# ServoShield_Protorype.net
KiCad netlist of a schematic drawn in EAGLE
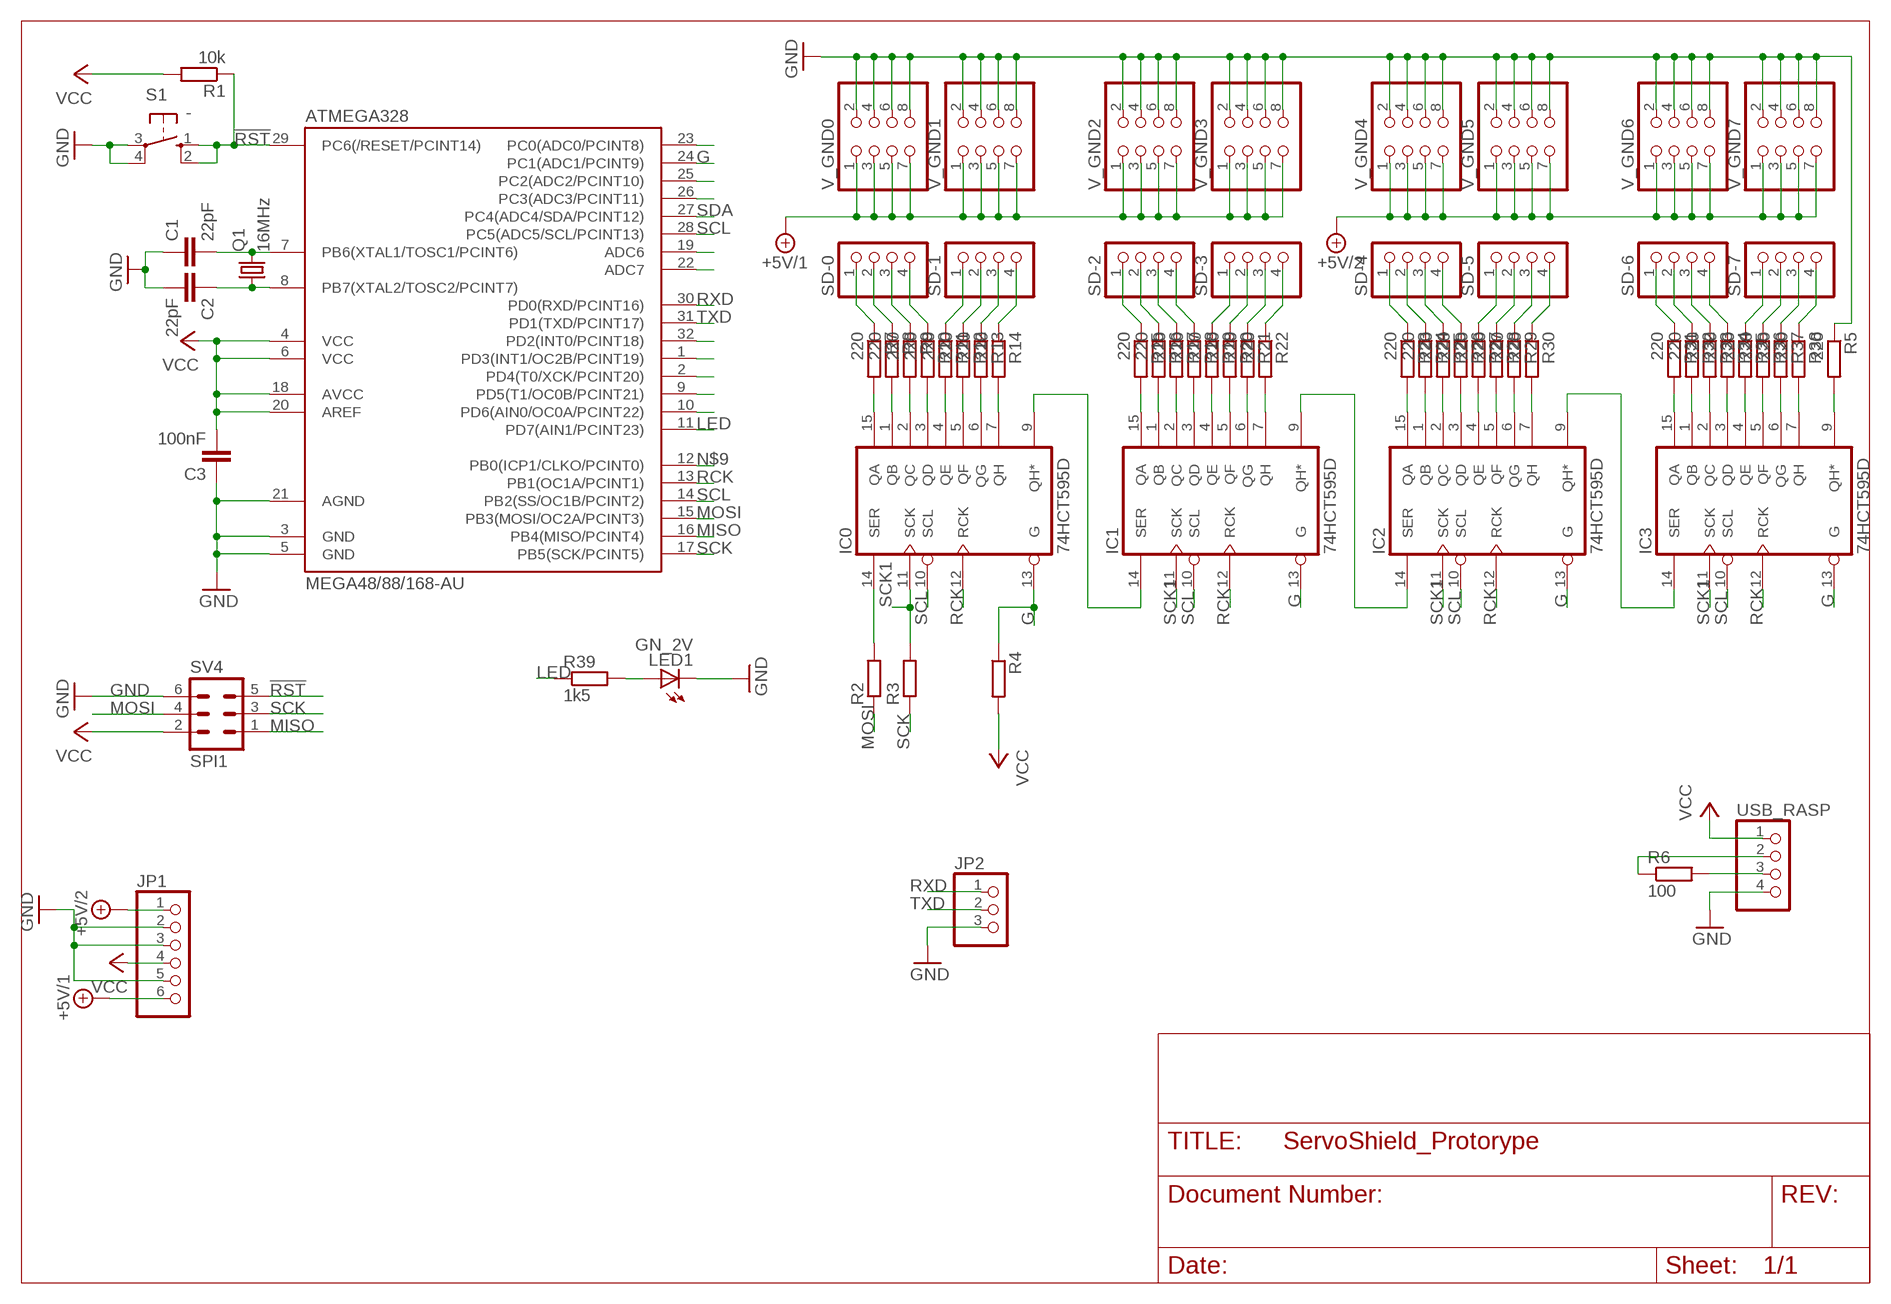
[diagram p0: schematic, sheet 1]

(export (version "E")
  (design (tool "Eeschema 10.0.6"))
  (components
    (comp (ref "ATMEGA328")
      (value "MEGA48/88/168-AU")
      (footprint "eagle-import:TQFP32-08")
      (libsource (lib "eagle-import") (part "MEGA48/88/168-AU"))
    )
    (comp (ref "C1")
      (value "22pF")
      (footprint "eagle-import:C0805")
      (libsource (lib "eagle-import") (part "C-EUC0805"))
    )
    (comp (ref "C2")
      (value "22pF")
      (footprint "eagle-import:C0805")
      (libsource (lib "eagle-import") (part "C-EUC0805"))
    )
    (comp (ref "C3")
      (value "100nF")
      (footprint "eagle-import:C0805")
      (libsource (lib "eagle-import") (part "resistor_C-EUC0805"))
    )
    (comp (ref "IC0")
      (value "74HCT595D")
      (footprint "eagle-import:SO16")
      (libsource (lib "eagle-import") (part "74595DHCT"))
    )
    (comp (ref "IC1")
      (value "74HCT595D")
      (footprint "eagle-import:SO16")
      (libsource (lib "eagle-import") (part "74595DHCT"))
    )
    (comp (ref "IC2")
      (value "74HCT595D")
      (footprint "eagle-import:SO16")
      (libsource (lib "eagle-import") (part "74595DHCT"))
    )
    (comp (ref "IC3")
      (value "74HCT595D")
      (footprint "eagle-import:SO16")
      (libsource (lib "eagle-import") (part "74595DHCT"))
    )
    (comp (ref "JP1")
      (value "PINHD-1X6")
      (footprint "eagle-import:1X06")
      (libsource (lib "eagle-import") (part "PINHD-1X6"))
    )
    (comp (ref "JP2")
      (value "PINHD-1X3")
      (footprint "eagle-import:1X03")
      (libsource (lib "eagle-import") (part "PINHD-1X3"))
    )
    (comp (ref "LED1")
      (value "GN_2V")
      (footprint "eagle-import:LED3MM")
      (libsource (lib "eagle-import") (part "LED3MM"))
    )
    (comp (ref "Q1")
      (value "16MHz")
      (footprint "eagle-import:HC49UP")
      (libsource (lib "eagle-import") (part "CRYSTALHC49UP"))
    )
    (comp (ref "R1")
      (value "10k")
      (footprint "eagle-import:R0805")
      (libsource (lib "eagle-import") (part "resistor_R-EU_R0805"))
    )
    (comp (ref "R2")
      (value "R-EU_R0805")
      (footprint "eagle-import:R0805")
      (libsource (lib "eagle-import") (part "R-EU_R0805"))
    )
    (comp (ref "R3")
      (value "R-EU_R0805")
      (footprint "eagle-import:R0805")
      (libsource (lib "eagle-import") (part "R-EU_R0805"))
    )
    (comp (ref "R4")
      (value "R-EU_R0805")
      (footprint "eagle-import:R0805")
      (libsource (lib "eagle-import") (part "R-EU_R0805"))
    )
    (comp (ref "R5")
      (value "220")
      (footprint "eagle-import:R0805")
      (libsource (lib "eagle-import") (part "R-EU_R0805"))
    )
    (comp (ref "R6")
      (value "100")
      (footprint "eagle-import:R0805")
      (libsource (lib "eagle-import") (part "R-EU_R0805"))
    )
    (comp (ref "R7")
      (value "220")
      (footprint "eagle-import:R0805")
      (libsource (lib "eagle-import") (part "R-EU_R0805"))
    )
    (comp (ref "R8")
      (value "220")
      (footprint "eagle-import:R0805")
      (libsource (lib "eagle-import") (part "R-EU_R0805"))
    )
    (comp (ref "R9")
      (value "220")
      (footprint "eagle-import:R0805")
      (libsource (lib "eagle-import") (part "R-EU_R0805"))
    )
    (comp (ref "R10")
      (value "220")
      (footprint "eagle-import:R0805")
      (libsource (lib "eagle-import") (part "R-EU_R0805"))
    )
    (comp (ref "R11")
      (value "220")
      (footprint "eagle-import:R0805")
      (libsource (lib "eagle-import") (part "R-EU_R0805"))
    )
    (comp (ref "R12")
      (value "220")
      (footprint "eagle-import:R0805")
      (libsource (lib "eagle-import") (part "R-EU_R0805"))
    )
    (comp (ref "R13")
      (value "220")
      (footprint "eagle-import:R0805")
      (libsource (lib "eagle-import") (part "R-EU_R0805"))
    )
    (comp (ref "R14")
      (value "220")
      (footprint "eagle-import:R0805")
      (libsource (lib "eagle-import") (part "R-EU_R0805"))
    )
    (comp (ref "R15")
      (value "220")
      (footprint "eagle-import:R0805")
      (libsource (lib "eagle-import") (part "R-EU_R0805"))
    )
    (comp (ref "R16")
      (value "220")
      (footprint "eagle-import:R0805")
      (libsource (lib "eagle-import") (part "R-EU_R0805"))
    )
    (comp (ref "R17")
      (value "220")
      (footprint "eagle-import:R0805")
      (libsource (lib "eagle-import") (part "R-EU_R0805"))
    )
    (comp (ref "R18")
      (value "220")
      (footprint "eagle-import:R0805")
      (libsource (lib "eagle-import") (part "R-EU_R0805"))
    )
    (comp (ref "R19")
      (value "220")
      (footprint "eagle-import:R0805")
      (libsource (lib "eagle-import") (part "R-EU_R0805"))
    )
    (comp (ref "R20")
      (value "220")
      (footprint "eagle-import:R0805")
      (libsource (lib "eagle-import") (part "R-EU_R0805"))
    )
    (comp (ref "R21")
      (value "220")
      (footprint "eagle-import:R0805")
      (libsource (lib "eagle-import") (part "R-EU_R0805"))
    )
    (comp (ref "R22")
      (value "220")
      (footprint "eagle-import:R0805")
      (libsource (lib "eagle-import") (part "R-EU_R0805"))
    )
    (comp (ref "R23")
      (value "220")
      (footprint "eagle-import:R0805")
      (libsource (lib "eagle-import") (part "R-EU_R0805"))
    )
    (comp (ref "R24")
      (value "220")
      (footprint "eagle-import:R0805")
      (libsource (lib "eagle-import") (part "R-EU_R0805"))
    )
    (comp (ref "R25")
      (value "220")
      (footprint "eagle-import:R0805")
      (libsource (lib "eagle-import") (part "R-EU_R0805"))
    )
    (comp (ref "R26")
      (value "220")
      (footprint "eagle-import:R0805")
      (libsource (lib "eagle-import") (part "R-EU_R0805"))
    )
    (comp (ref "R27")
      (value "220")
      (footprint "eagle-import:R0805")
      (libsource (lib "eagle-import") (part "R-EU_R0805"))
    )
    (comp (ref "R28")
      (value "220")
      (footprint "eagle-import:R0805")
      (libsource (lib "eagle-import") (part "R-EU_R0805"))
    )
    (comp (ref "R29")
      (value "220")
      (footprint "eagle-import:R0805")
      (libsource (lib "eagle-import") (part "R-EU_R0805"))
    )
    (comp (ref "R30")
      (value "220")
      (footprint "eagle-import:R0805")
      (libsource (lib "eagle-import") (part "R-EU_R0805"))
    )
    (comp (ref "R31")
      (value "220")
      (footprint "eagle-import:R0805")
      (libsource (lib "eagle-import") (part "R-EU_R0805"))
    )
    (comp (ref "R32")
      (value "220")
      (footprint "eagle-import:R0805")
      (libsource (lib "eagle-import") (part "R-EU_R0805"))
    )
    (comp (ref "R33")
      (value "220")
      (footprint "eagle-import:R0805")
      (libsource (lib "eagle-import") (part "R-EU_R0805"))
    )
    (comp (ref "R34")
      (value "220")
      (footprint "eagle-import:R0805")
      (libsource (lib "eagle-import") (part "R-EU_R0805"))
    )
    (comp (ref "R35")
      (value "220")
      (footprint "eagle-import:R0805")
      (libsource (lib "eagle-import") (part "R-EU_R0805"))
    )
    (comp (ref "R36")
      (value "220")
      (footprint "eagle-import:R0805")
      (libsource (lib "eagle-import") (part "R-EU_R0805"))
    )
    (comp (ref "R37")
      (value "220")
      (footprint "eagle-import:R0805")
      (libsource (lib "eagle-import") (part "R-EU_R0805"))
    )
    (comp (ref "R38")
      (value "220")
      (footprint "eagle-import:R0805")
      (libsource (lib "eagle-import") (part "R-EU_R0805"))
    )
    (comp (ref "R39")
      (value "1k5")
      (footprint "eagle-import:R0805")
      (libsource (lib "eagle-import") (part "R-EU_R0805"))
    )
    (comp (ref "S1")
      (value "-")
      (footprint "eagle-import:B3F-10XX")
      (fields (field (name "MPN") "B3F-1000"))
      (libsource (lib "eagle-import") (part "10-XX"))
    )
    (comp (ref "SD-0")
      (value "PINHD-1X4")
      (footprint "eagle-import:1X04")
      (libsource (lib "eagle-import") (part "PINHD-1X4"))
    )
    (comp (ref "SD-1")
      (value "PINHD-1X4")
      (footprint "eagle-import:1X04")
      (libsource (lib "eagle-import") (part "PINHD-1X4"))
    )
    (comp (ref "SD-2")
      (value "PINHD-1X4")
      (footprint "eagle-import:1X04")
      (libsource (lib "eagle-import") (part "PINHD-1X4"))
    )
    (comp (ref "SD-3")
      (value "PINHD-1X4")
      (footprint "eagle-import:1X04")
      (libsource (lib "eagle-import") (part "PINHD-1X4"))
    )
    (comp (ref "SD-4")
      (value "PINHD-1X4")
      (footprint "eagle-import:1X04")
      (libsource (lib "eagle-import") (part "PINHD-1X4"))
    )
    (comp (ref "SD-5")
      (value "PINHD-1X4")
      (footprint "eagle-import:1X04")
      (libsource (lib "eagle-import") (part "PINHD-1X4"))
    )
    (comp (ref "SD-6")
      (value "PINHD-1X4")
      (footprint "eagle-import:1X04")
      (libsource (lib "eagle-import") (part "PINHD-1X4"))
    )
    (comp (ref "SD-7")
      (value "PINHD-1X4")
      (footprint "eagle-import:1X04")
      (libsource (lib "eagle-import") (part "PINHD-1X4"))
    )
    (comp (ref "SV4")
      (value "SPI1")
      (footprint "eagle-import:ML6")
      (libsource (lib "eagle-import") (part "ML6"))
    )
    (comp (ref "USB_RASP")
      (value "PINHD-1X4")
      (footprint "eagle-import:1X04")
      (libsource (lib "eagle-import") (part "PINHD-1X4"))
    )
    (comp (ref "V_GND0")
      (value "PINHD-2X4")
      (footprint "eagle-import:2X04")
      (libsource (lib "eagle-import") (part "PINHD-2X4"))
    )
    (comp (ref "V_GND1")
      (value "PINHD-2X4")
      (footprint "eagle-import:2X04")
      (libsource (lib "eagle-import") (part "PINHD-2X4"))
    )
    (comp (ref "V_GND2")
      (value "PINHD-2X4")
      (footprint "eagle-import:2X04")
      (libsource (lib "eagle-import") (part "PINHD-2X4"))
    )
    (comp (ref "V_GND3")
      (value "PINHD-2X4")
      (footprint "eagle-import:2X04")
      (libsource (lib "eagle-import") (part "PINHD-2X4"))
    )
    (comp (ref "V_GND4")
      (value "PINHD-2X4")
      (footprint "eagle-import:2X04")
      (libsource (lib "eagle-import") (part "PINHD-2X4"))
    )
    (comp (ref "V_GND5")
      (value "PINHD-2X4")
      (footprint "eagle-import:2X04")
      (libsource (lib "eagle-import") (part "PINHD-2X4"))
    )
    (comp (ref "V_GND6")
      (value "PINHD-2X4")
      (footprint "eagle-import:2X04")
      (libsource (lib "eagle-import") (part "PINHD-2X4"))
    )
    (comp (ref "V_GND7")
      (value "PINHD-2X4")
      (footprint "eagle-import:2X04")
      (libsource (lib "eagle-import") (part "PINHD-2X4"))
    )
  )
  (nets
    (net (code "1") (name "+5V{slash}1") (class "Default")
      (node (ref "JP1") (pin "6") (pinfunction "6_6") (pintype "passive"))
      (node (ref "V_GND0") (pin "1") (pinfunction "1_1") (pintype "passive"))
      (node (ref "V_GND0") (pin "3") (pinfunction "3_3") (pintype "passive"))
      (node (ref "V_GND0") (pin "5") (pinfunction "5_5") (pintype "passive"))
      (node (ref "V_GND0") (pin "7") (pinfunction "7_7") (pintype "passive"))
      (node (ref "V_GND1") (pin "1") (pinfunction "1_1") (pintype "passive"))
      (node (ref "V_GND1") (pin "3") (pinfunction "3_3") (pintype "passive"))
      (node (ref "V_GND1") (pin "5") (pinfunction "5_5") (pintype "passive"))
      (node (ref "V_GND1") (pin "7") (pinfunction "7_7") (pintype "passive"))
      (node (ref "V_GND2") (pin "1") (pinfunction "1_1") (pintype "passive"))
      (node (ref "V_GND2") (pin "3") (pinfunction "3_3") (pintype "passive"))
      (node (ref "V_GND2") (pin "5") (pinfunction "5_5") (pintype "passive"))
      (node (ref "V_GND2") (pin "7") (pinfunction "7_7") (pintype "passive"))
      (node (ref "V_GND3") (pin "1") (pinfunction "1_1") (pintype "passive"))
      (node (ref "V_GND3") (pin "3") (pinfunction "3_3") (pintype "passive"))
      (node (ref "V_GND3") (pin "5") (pinfunction "5_5") (pintype "passive"))
      (node (ref "V_GND3") (pin "7") (pinfunction "7_7") (pintype "passive"))
    )
    (net (code "2") (name "+5V{slash}2") (class "Default")
      (node (ref "JP1") (pin "1") (pinfunction "1_1") (pintype "passive"))
      (node (ref "V_GND4") (pin "1") (pinfunction "1_1") (pintype "passive"))
      (node (ref "V_GND4") (pin "3") (pinfunction "3_3") (pintype "passive"))
      (node (ref "V_GND4") (pin "5") (pinfunction "5_5") (pintype "passive"))
      (node (ref "V_GND4") (pin "7") (pinfunction "7_7") (pintype "passive"))
      (node (ref "V_GND5") (pin "1") (pinfunction "1_1") (pintype "passive"))
      (node (ref "V_GND5") (pin "3") (pinfunction "3_3") (pintype "passive"))
      (node (ref "V_GND5") (pin "5") (pinfunction "5_5") (pintype "passive"))
      (node (ref "V_GND5") (pin "7") (pinfunction "7_7") (pintype "passive"))
      (node (ref "V_GND6") (pin "1") (pinfunction "1_1") (pintype "passive"))
      (node (ref "V_GND6") (pin "3") (pinfunction "3_3") (pintype "passive"))
      (node (ref "V_GND6") (pin "5") (pinfunction "5_5") (pintype "passive"))
      (node (ref "V_GND6") (pin "7") (pinfunction "7_7") (pintype "passive"))
      (node (ref "V_GND7") (pin "1") (pinfunction "1_1") (pintype "passive"))
      (node (ref "V_GND7") (pin "3") (pinfunction "3_3") (pintype "passive"))
      (node (ref "V_GND7") (pin "5") (pinfunction "5_5") (pintype "passive"))
      (node (ref "V_GND7") (pin "7") (pinfunction "7_7") (pintype "passive"))
    )
    (net (code "3") (name "/G") (class "Default")
      (node (ref "ATMEGA328") (pin "24") (pinfunction "PC1(ADC1/PCINT9)_24") (pintype "bidirectional"))
      (node (ref "IC0") (pin "13") (pinfunction "G_13") (pintype "input"))
      (node (ref "IC1") (pin "13") (pinfunction "G_13") (pintype "input"))
      (node (ref "IC2") (pin "13") (pinfunction "G_13") (pintype "input"))
      (node (ref "IC3") (pin "13") (pinfunction "G_13") (pintype "input"))
      (node (ref "R4") (pin "1") (pinfunction "1_1") (pintype "passive"))
    )
    (net (code "4") (name "/LED") (class "Default")
      (node (ref "ATMEGA328") (pin "11") (pinfunction "PD7(AIN1/PCINT23)_11") (pintype "bidirectional"))
      (node (ref "R39") (pin "1") (pinfunction "1_1") (pintype "passive"))
    )
    (net (code "5") (name "/MISO") (class "Default")
      (node (ref "ATMEGA328") (pin "16") (pinfunction "PB4(MISO/PCINT4)_16") (pintype "bidirectional"))
      (node (ref "SV4") (pin "1") (pinfunction "1_1") (pintype "passive"))
    )
    (net (code "6") (name "/MOSI") (class "Default")
      (node (ref "ATMEGA328") (pin "15") (pinfunction "PB3(MOSI/OC2A/PCINT3)_15") (pintype "bidirectional"))
      (node (ref "R2") (pin "1") (pinfunction "1_1") (pintype "passive"))
      (node (ref "SV4") (pin "4") (pinfunction "4_4") (pintype "passive"))
    )
    (net (code "7") (name "/N$9") (class "Default")
      (node (ref "ATMEGA328") (pin "12") (pinfunction "PB0(ICP1/CLKO/PCINT0)_12") (pintype "bidirectional"))
    )
    (net (code "8") (name "/RCK") (class "Default")
      (node (ref "ATMEGA328") (pin "13") (pinfunction "PB1(OC1A/PCINT1)_13") (pintype "bidirectional"))
      (node (ref "IC0") (pin "12") (pinfunction "RCK_12") (pintype "input"))
      (node (ref "IC1") (pin "12") (pinfunction "RCK_12") (pintype "input"))
      (node (ref "IC2") (pin "12") (pinfunction "RCK_12") (pintype "input"))
      (node (ref "IC3") (pin "12") (pinfunction "RCK_12") (pintype "input"))
    )
    (net (code "9") (name "/RXD") (class "Default")
      (node (ref "ATMEGA328") (pin "30") (pinfunction "PD0(RXD/PCINT16)_30") (pintype "bidirectional"))
      (node (ref "JP2") (pin "1") (pinfunction "1_1") (pintype "passive"))
    )
    (net (code "10") (name "/SCK") (class "Default")
      (node (ref "ATMEGA328") (pin "17") (pinfunction "PB5(SCK/PCINT5)_17") (pintype "bidirectional"))
      (node (ref "R3") (pin "1") (pinfunction "1_1") (pintype "passive"))
      (node (ref "SV4") (pin "3") (pinfunction "3_3") (pintype "passive"))
    )
    (net (code "11") (name "/SCK1") (class "Default")
      (node (ref "IC0") (pin "11") (pinfunction "SCK_11") (pintype "input"))
      (node (ref "IC1") (pin "11") (pinfunction "SCK_11") (pintype "input"))
      (node (ref "IC2") (pin "11") (pinfunction "SCK_11") (pintype "input"))
      (node (ref "IC3") (pin "11") (pinfunction "SCK_11") (pintype "input"))
      (node (ref "R3") (pin "2") (pinfunction "2_2") (pintype "passive"))
    )
    (net (code "12") (name "/SCL") (class "Default")
      (node (ref "ATMEGA328") (pin "14") (pinfunction "PB2(SS/OC1B/PCINT2)_14") (pintype "bidirectional"))
      (node (ref "ATMEGA328") (pin "28") (pinfunction "PC5(ADC5/SCL/PCINT13)_28") (pintype "bidirectional"))
      (node (ref "IC0") (pin "10") (pinfunction "SCL_10") (pintype "input"))
      (node (ref "IC1") (pin "10") (pinfunction "SCL_10") (pintype "input"))
      (node (ref "IC2") (pin "10") (pinfunction "SCL_10") (pintype "input"))
      (node (ref "IC3") (pin "10") (pinfunction "SCL_10") (pintype "input"))
    )
    (net (code "13") (name "/SDA") (class "Default")
      (node (ref "ATMEGA328") (pin "27") (pinfunction "PC4(ADC4/SDA/PCINT12)_27") (pintype "bidirectional"))
    )
    (net (code "14") (name "/TXD") (class "Default")
      (node (ref "ATMEGA328") (pin "31") (pinfunction "PD1(TXD/PCINT17)_31") (pintype "bidirectional"))
      (node (ref "JP2") (pin "2") (pinfunction "2_2") (pintype "passive"))
    )
    (net (code "15") (name "/~{RST}") (class "Default")
      (node (ref "ATMEGA328") (pin "29") (pinfunction "PC6(/RESET/PCINT14)_29") (pintype "bidirectional"))
      (node (ref "R1") (pin "1") (pinfunction "1_1") (pintype "passive"))
      (node (ref "S1") (pin "1") (pinfunction "S_1") (pintype "passive"))
      (node (ref "S1") (pin "2") (pinfunction "S1_2") (pintype "passive"))
      (node (ref "SV4") (pin "5") (pinfunction "5_5") (pintype "passive"))
    )
    (net (code "16") (name "GND") (class "Default")
      (node (ref "ATMEGA328") (pin "21") (pinfunction "AGND_21") (pintype "power_in"))
      (node (ref "ATMEGA328") (pin "3") (pinfunction "GND_3") (pintype "power_in"))
      (node (ref "ATMEGA328") (pin "5") (pinfunction "GND_5") (pintype "power_in"))
      (node (ref "C1") (pin "1") (pinfunction "1_1") (pintype "passive"))
      (node (ref "C2") (pin "2") (pinfunction "2_2") (pintype "passive"))
      (node (ref "C3") (pin "1") (pinfunction "1_1") (pintype "passive"))
      (node (ref "JP1") (pin "2") (pinfunction "2_2") (pintype "passive"))
      (node (ref "JP1") (pin "3") (pinfunction "3_3") (pintype "passive"))
      (node (ref "JP1") (pin "5") (pinfunction "5_5") (pintype "passive"))
      (node (ref "JP2") (pin "3") (pinfunction "3_3") (pintype "passive"))
      (node (ref "LED1") (pin "K") (pinfunction "C_K") (pintype "passive"))
      (node (ref "R5") (pin "1") (pinfunction "1_1") (pintype "passive"))
      (node (ref "S1") (pin "3") (pinfunction "P_3") (pintype "passive"))
      (node (ref "S1") (pin "4") (pinfunction "P1_4") (pintype "passive"))
      (node (ref "SV4") (pin "6") (pinfunction "6_6") (pintype "passive"))
      (node (ref "USB_RASP") (pin "4") (pinfunction "4_4") (pintype "passive"))
      (node (ref "V_GND0") (pin "2") (pinfunction "2_2") (pintype "passive"))
      (node (ref "V_GND0") (pin "4") (pinfunction "4_4") (pintype "passive"))
      (node (ref "V_GND0") (pin "6") (pinfunction "6_6") (pintype "passive"))
      (node (ref "V_GND0") (pin "8") (pinfunction "8_8") (pintype "passive"))
      (node (ref "V_GND1") (pin "2") (pinfunction "2_2") (pintype "passive"))
      (node (ref "V_GND1") (pin "4") (pinfunction "4_4") (pintype "passive"))
      (node (ref "V_GND1") (pin "6") (pinfunction "6_6") (pintype "passive"))
      (node (ref "V_GND1") (pin "8") (pinfunction "8_8") (pintype "passive"))
      (node (ref "V_GND2") (pin "2") (pinfunction "2_2") (pintype "passive"))
      (node (ref "V_GND2") (pin "4") (pinfunction "4_4") (pintype "passive"))
      (node (ref "V_GND2") (pin "6") (pinfunction "6_6") (pintype "passive"))
      (node (ref "V_GND2") (pin "8") (pinfunction "8_8") (pintype "passive"))
      (node (ref "V_GND3") (pin "2") (pinfunction "2_2") (pintype "passive"))
      (node (ref "V_GND3") (pin "4") (pinfunction "4_4") (pintype "passive"))
      (node (ref "V_GND3") (pin "6") (pinfunction "6_6") (pintype "passive"))
      (node (ref "V_GND3") (pin "8") (pinfunction "8_8") (pintype "passive"))
      (node (ref "V_GND4") (pin "2") (pinfunction "2_2") (pintype "passive"))
      (node (ref "V_GND4") (pin "4") (pinfunction "4_4") (pintype "passive"))
      (node (ref "V_GND4") (pin "6") (pinfunction "6_6") (pintype "passive"))
      (node (ref "V_GND4") (pin "8") (pinfunction "8_8") (pintype "passive"))
      (node (ref "V_GND5") (pin "2") (pinfunction "2_2") (pintype "passive"))
      (node (ref "V_GND5") (pin "4") (pinfunction "4_4") (pintype "passive"))
      (node (ref "V_GND5") (pin "6") (pinfunction "6_6") (pintype "passive"))
      (node (ref "V_GND5") (pin "8") (pinfunction "8_8") (pintype "passive"))
      (node (ref "V_GND6") (pin "2") (pinfunction "2_2") (pintype "passive"))
      (node (ref "V_GND6") (pin "4") (pinfunction "4_4") (pintype "passive"))
      (node (ref "V_GND6") (pin "6") (pinfunction "6_6") (pintype "passive"))
      (node (ref "V_GND6") (pin "8") (pinfunction "8_8") (pintype "passive"))
      (node (ref "V_GND7") (pin "2") (pinfunction "2_2") (pintype "passive"))
      (node (ref "V_GND7") (pin "4") (pinfunction "4_4") (pintype "passive"))
      (node (ref "V_GND7") (pin "6") (pinfunction "6_6") (pintype "passive"))
      (node (ref "V_GND7") (pin "8") (pinfunction "8_8") (pintype "passive"))
    )
    (net (code "17") (name "Net-(ATMEGA328-PB6(XTAL1{slash}TOSC1{slash}PCINT6))") (class "Default")
      (node (ref "ATMEGA328") (pin "7") (pinfunction "PB6(XTAL1/TOSC1/PCINT6)_7") (pintype "bidirectional"))
      (node (ref "C1") (pin "2") (pinfunction "2_2") (pintype "passive"))
      (node (ref "Q1") (pin "2") (pinfunction "2_2") (pintype "passive"))
    )
    (net (code "18") (name "Net-(ATMEGA328-PB7(XTAL2{slash}TOSC2{slash}PCINT7))") (class "Default")
      (node (ref "ATMEGA328") (pin "8") (pinfunction "PB7(XTAL2/TOSC2/PCINT7)_8") (pintype "bidirectional"))
      (node (ref "C2") (pin "1") (pinfunction "1_1") (pintype "passive"))
      (node (ref "Q1") (pin "1") (pinfunction "1_1") (pintype "passive"))
    )
    (net (code "19") (name "Net-(IC0A-QA)") (class "Default")
      (node (ref "IC0") (pin "15") (pinfunction "QA_15") (pintype "tri_state"))
      (node (ref "R7") (pin "2") (pinfunction "2_2") (pintype "passive"))
    )
    (net (code "20") (name "Net-(IC0A-QB)") (class "Default")
      (node (ref "IC0") (pin "1") (pinfunction "QB_1") (pintype "tri_state"))
      (node (ref "R8") (pin "2") (pinfunction "2_2") (pintype "passive"))
    )
    (net (code "21") (name "Net-(IC0A-QC)") (class "Default")
      (node (ref "IC0") (pin "2") (pinfunction "QC_2") (pintype "tri_state"))
      (node (ref "R9") (pin "2") (pinfunction "2_2") (pintype "passive"))
    )
    (net (code "22") (name "Net-(IC0A-QD)") (class "Default")
      (node (ref "IC0") (pin "3") (pinfunction "QD_3") (pintype "tri_state"))
      (node (ref "R10") (pin "2") (pinfunction "2_2") (pintype "passive"))
    )
    (net (code "23") (name "Net-(IC0A-QE)") (class "Default")
      (node (ref "IC0") (pin "4") (pinfunction "QE_4") (pintype "tri_state"))
      (node (ref "R11") (pin "2") (pinfunction "2_2") (pintype "passive"))
    )
    (net (code "24") (name "Net-(IC0A-QF)") (class "Default")
      (node (ref "IC0") (pin "5") (pinfunction "QF_5") (pintype "tri_state"))
      (node (ref "R12") (pin "2") (pinfunction "2_2") (pintype "passive"))
    )
    (net (code "25") (name "Net-(IC0A-QG)") (class "Default")
      (node (ref "IC0") (pin "6") (pinfunction "QG_6") (pintype "tri_state"))
      (node (ref "R13") (pin "2") (pinfunction "2_2") (pintype "passive"))
    )
    (net (code "26") (name "Net-(IC0A-QH)") (class "Default")
      (node (ref "IC0") (pin "7") (pinfunction "QH_7") (pintype "tri_state"))
      (node (ref "R14") (pin "2") (pinfunction "2_2") (pintype "passive"))
    )
    (net (code "27") (name "Net-(IC0A-QH*)") (class "Default")
      (node (ref "IC0") (pin "9") (pinfunction "QH*_9") (pintype "tri_state"))
      (node (ref "IC1") (pin "14") (pinfunction "SER_14") (pintype "input"))
    )
    (net (code "28") (name "Net-(IC0A-SER)") (class "Default")
      (node (ref "IC0") (pin "14") (pinfunction "SER_14") (pintype "input"))
      (node (ref "R2") (pin "2") (pinfunction "2_2") (pintype "passive"))
    )
    (net (code "29") (name "Net-(IC1A-QA)") (class "Default")
      (node (ref "IC1") (pin "15") (pinfunction "QA_15") (pintype "tri_state"))
      (node (ref "R15") (pin "2") (pinfunction "2_2") (pintype "passive"))
    )
    (net (code "30") (name "Net-(IC1A-QB)") (class "Default")
      (node (ref "IC1") (pin "1") (pinfunction "QB_1") (pintype "tri_state"))
      (node (ref "R16") (pin "2") (pinfunction "2_2") (pintype "passive"))
    )
    (net (code "31") (name "Net-(IC1A-QC)") (class "Default")
      (node (ref "IC1") (pin "2") (pinfunction "QC_2") (pintype "tri_state"))
      (node (ref "R17") (pin "2") (pinfunction "2_2") (pintype "passive"))
    )
    (net (code "32") (name "Net-(IC1A-QD)") (class "Default")
      (node (ref "IC1") (pin "3") (pinfunction "QD_3") (pintype "tri_state"))
      (node (ref "R18") (pin "2") (pinfunction "2_2") (pintype "passive"))
    )
    (net (code "33") (name "Net-(IC1A-QE)") (class "Default")
      (node (ref "IC1") (pin "4") (pinfunction "QE_4") (pintype "tri_state"))
      (node (ref "R19") (pin "2") (pinfunction "2_2") (pintype "passive"))
    )
    (net (code "34") (name "Net-(IC1A-QF)") (class "Default")
      (node (ref "IC1") (pin "5") (pinfunction "QF_5") (pintype "tri_state"))
      (node (ref "R20") (pin "2") (pinfunction "2_2") (pintype "passive"))
    )
    (net (code "35") (name "Net-(IC1A-QG)") (class "Default")
      (node (ref "IC1") (pin "6") (pinfunction "QG_6") (pintype "tri_state"))
      (node (ref "R21") (pin "2") (pinfunction "2_2") (pintype "passive"))
    )
    (net (code "36") (name "Net-(IC1A-QH)") (class "Default")
      (node (ref "IC1") (pin "7") (pinfunction "QH_7") (pintype "tri_state"))
      (node (ref "R22") (pin "2") (pinfunction "2_2") (pintype "passive"))
    )
    (net (code "37") (name "Net-(IC1A-QH*)") (class "Default")
      (node (ref "IC1") (pin "9") (pinfunction "QH*_9") (pintype "tri_state"))
      (node (ref "IC2") (pin "14") (pinfunction "SER_14") (pintype "input"))
    )
    (net (code "38") (name "Net-(IC2A-QA)") (class "Default")
      (node (ref "IC2") (pin "15") (pinfunction "QA_15") (pintype "tri_state"))
      (node (ref "R23") (pin "2") (pinfunction "2_2") (pintype "passive"))
    )
    (net (code "39") (name "Net-(IC2A-QB)") (class "Default")
      (node (ref "IC2") (pin "1") (pinfunction "QB_1") (pintype "tri_state"))
      (node (ref "R24") (pin "2") (pinfunction "2_2") (pintype "passive"))
    )
    (net (code "40") (name "Net-(IC2A-QC)") (class "Default")
      (node (ref "IC2") (pin "2") (pinfunction "QC_2") (pintype "tri_state"))
      (node (ref "R25") (pin "2") (pinfunction "2_2") (pintype "passive"))
    )
    (net (code "41") (name "Net-(IC2A-QD)") (class "Default")
      (node (ref "IC2") (pin "3") (pinfunction "QD_3") (pintype "tri_state"))
      (node (ref "R26") (pin "2") (pinfunction "2_2") (pintype "passive"))
    )
    (net (code "42") (name "Net-(IC2A-QE)") (class "Default")
      (node (ref "IC2") (pin "4") (pinfunction "QE_4") (pintype "tri_state"))
      (node (ref "R27") (pin "2") (pinfunction "2_2") (pintype "passive"))
    )
    (net (code "43") (name "Net-(IC2A-QF)") (class "Default")
      (node (ref "IC2") (pin "5") (pinfunction "QF_5") (pintype "tri_state"))
      (node (ref "R28") (pin "2") (pinfunction "2_2") (pintype "passive"))
    )
    (net (code "44") (name "Net-(IC2A-QG)") (class "Default")
      (node (ref "IC2") (pin "6") (pinfunction "QG_6") (pintype "tri_state"))
      (node (ref "R29") (pin "2") (pinfunction "2_2") (pintype "passive"))
    )
    (net (code "45") (name "Net-(IC2A-QH)") (class "Default")
      (node (ref "IC2") (pin "7") (pinfunction "QH_7") (pintype "tri_state"))
      (node (ref "R30") (pin "2") (pinfunction "2_2") (pintype "passive"))
    )
    (net (code "46") (name "Net-(IC2A-QH*)") (class "Default")
      (node (ref "IC2") (pin "9") (pinfunction "QH*_9") (pintype "tri_state"))
      (node (ref "IC3") (pin "14") (pinfunction "SER_14") (pintype "input"))
    )
    (net (code "47") (name "Net-(IC3A-QA)") (class "Default")
      (node (ref "IC3") (pin "15") (pinfunction "QA_15") (pintype "tri_state"))
      (node (ref "R31") (pin "2") (pinfunction "2_2") (pintype "passive"))
    )
    (net (code "48") (name "Net-(IC3A-QB)") (class "Default")
      (node (ref "IC3") (pin "1") (pinfunction "QB_1") (pintype "tri_state"))
      (node (ref "R32") (pin "2") (pinfunction "2_2") (pintype "passive"))
    )
    (net (code "49") (name "Net-(IC3A-QC)") (class "Default")
      (node (ref "IC3") (pin "2") (pinfunction "QC_2") (pintype "tri_state"))
      (node (ref "R33") (pin "2") (pinfunction "2_2") (pintype "passive"))
    )
    (net (code "50") (name "Net-(IC3A-QD)") (class "Default")
      (node (ref "IC3") (pin "3") (pinfunction "QD_3") (pintype "tri_state"))
      (node (ref "R34") (pin "2") (pinfunction "2_2") (pintype "passive"))
    )
    (net (code "51") (name "Net-(IC3A-QE)") (class "Default")
      (node (ref "IC3") (pin "4") (pinfunction "QE_4") (pintype "tri_state"))
      (node (ref "R35") (pin "2") (pinfunction "2_2") (pintype "passive"))
    )
    (net (code "52") (name "Net-(IC3A-QF)") (class "Default")
      (node (ref "IC3") (pin "5") (pinfunction "QF_5") (pintype "tri_state"))
      (node (ref "R36") (pin "2") (pinfunction "2_2") (pintype "passive"))
    )
    (net (code "53") (name "Net-(IC3A-QG)") (class "Default")
      (node (ref "IC3") (pin "6") (pinfunction "QG_6") (pintype "tri_state"))
      (node (ref "R37") (pin "2") (pinfunction "2_2") (pintype "passive"))
    )
    (net (code "54") (name "Net-(IC3A-QH)") (class "Default")
      (node (ref "IC3") (pin "7") (pinfunction "QH_7") (pintype "tri_state"))
      (node (ref "R38") (pin "2") (pinfunction "2_2") (pintype "passive"))
    )
    (net (code "55") (name "Net-(IC3A-QH*)") (class "Default")
      (node (ref "IC3") (pin "9") (pinfunction "QH*_9") (pintype "tri_state"))
      (node (ref "R5") (pin "2") (pinfunction "2_2") (pintype "passive"))
    )
    (net (code "56") (name "Net-(LED1-PadA)") (class "Default")
      (node (ref "LED1") (pin "A") (pinfunction "A_A") (pintype "passive"))
      (node (ref "R39") (pin "2") (pinfunction "2_2") (pintype "passive"))
    )
    (net (code "57") (name "Net-(R6-Pad1)") (class "Default")
      (node (ref "R6") (pin "1") (pinfunction "1_1") (pintype "passive"))
      (node (ref "USB_RASP") (pin "2") (pinfunction "2_2") (pintype "passive"))
    )
    (net (code "58") (name "Net-(R6-Pad2)") (class "Default")
      (node (ref "R6") (pin "2") (pinfunction "2_2") (pintype "passive"))
      (node (ref "USB_RASP") (pin "3") (pinfunction "3_3") (pintype "passive"))
    )
    (net (code "59") (name "Net-(R7-Pad1)") (class "Default")
      (node (ref "R7") (pin "1") (pinfunction "1_1") (pintype "passive"))
      (node (ref "SD-0") (pin "1") (pinfunction "1_1") (pintype "passive"))
    )
    (net (code "60") (name "Net-(R8-Pad1)") (class "Default")
      (node (ref "R8") (pin "1") (pinfunction "1_1") (pintype "passive"))
      (node (ref "SD-0") (pin "2") (pinfunction "2_2") (pintype "passive"))
    )
    (net (code "61") (name "Net-(R9-Pad1)") (class "Default")
      (node (ref "R9") (pin "1") (pinfunction "1_1") (pintype "passive"))
      (node (ref "SD-0") (pin "3") (pinfunction "3_3") (pintype "passive"))
    )
    (net (code "62") (name "Net-(R10-Pad1)") (class "Default")
      (node (ref "R10") (pin "1") (pinfunction "1_1") (pintype "passive"))
      (node (ref "SD-0") (pin "4") (pinfunction "4_4") (pintype "passive"))
    )
    (net (code "63") (name "Net-(R11-Pad1)") (class "Default")
      (node (ref "R11") (pin "1") (pinfunction "1_1") (pintype "passive"))
      (node (ref "SD-1") (pin "1") (pinfunction "1_1") (pintype "passive"))
    )
    (net (code "64") (name "Net-(R12-Pad1)") (class "Default")
      (node (ref "R12") (pin "1") (pinfunction "1_1") (pintype "passive"))
      (node (ref "SD-1") (pin "2") (pinfunction "2_2") (pintype "passive"))
    )
    (net (code "65") (name "Net-(R13-Pad1)") (class "Default")
      (node (ref "R13") (pin "1") (pinfunction "1_1") (pintype "passive"))
      (node (ref "SD-1") (pin "3") (pinfunction "3_3") (pintype "passive"))
    )
    (net (code "66") (name "Net-(R14-Pad1)") (class "Default")
      (node (ref "R14") (pin "1") (pinfunction "1_1") (pintype "passive"))
      (node (ref "SD-1") (pin "4") (pinfunction "4_4") (pintype "passive"))
    )
    (net (code "67") (name "Net-(R15-Pad1)") (class "Default")
      (node (ref "R15") (pin "1") (pinfunction "1_1") (pintype "passive"))
      (node (ref "SD-2") (pin "1") (pinfunction "1_1") (pintype "passive"))
    )
    (net (code "68") (name "Net-(R16-Pad1)") (class "Default")
      (node (ref "R16") (pin "1") (pinfunction "1_1") (pintype "passive"))
      (node (ref "SD-2") (pin "2") (pinfunction "2_2") (pintype "passive"))
    )
    (net (code "69") (name "Net-(R17-Pad1)") (class "Default")
      (node (ref "R17") (pin "1") (pinfunction "1_1") (pintype "passive"))
      (node (ref "SD-2") (pin "3") (pinfunction "3_3") (pintype "passive"))
    )
    (net (code "70") (name "Net-(R18-Pad1)") (class "Default")
      (node (ref "R18") (pin "1") (pinfunction "1_1") (pintype "passive"))
      (node (ref "SD-2") (pin "4") (pinfunction "4_4") (pintype "passive"))
    )
    (net (code "71") (name "Net-(R19-Pad1)") (class "Default")
      (node (ref "R19") (pin "1") (pinfunction "1_1") (pintype "passive"))
      (node (ref "SD-3") (pin "1") (pinfunction "1_1") (pintype "passive"))
    )
    (net (code "72") (name "Net-(R20-Pad1)") (class "Default")
      (node (ref "R20") (pin "1") (pinfunction "1_1") (pintype "passive"))
      (node (ref "SD-3") (pin "2") (pinfunction "2_2") (pintype "passive"))
    )
    (net (code "73") (name "Net-(R21-Pad1)") (class "Default")
      (node (ref "R21") (pin "1") (pinfunction "1_1") (pintype "passive"))
      (node (ref "SD-3") (pin "3") (pinfunction "3_3") (pintype "passive"))
    )
    (net (code "74") (name "Net-(R22-Pad1)") (class "Default")
      (node (ref "R22") (pin "1") (pinfunction "1_1") (pintype "passive"))
      (node (ref "SD-3") (pin "4") (pinfunction "4_4") (pintype "passive"))
    )
    (net (code "75") (name "Net-(R23-Pad1)") (class "Default")
      (node (ref "R23") (pin "1") (pinfunction "1_1") (pintype "passive"))
      (node (ref "SD-4") (pin "1") (pinfunction "1_1") (pintype "passive"))
    )
    (net (code "76") (name "Net-(R24-Pad1)") (class "Default")
      (node (ref "R24") (pin "1") (pinfunction "1_1") (pintype "passive"))
      (node (ref "SD-4") (pin "2") (pinfunction "2_2") (pintype "passive"))
    )
    (net (code "77") (name "Net-(R25-Pad1)") (class "Default")
      (node (ref "R25") (pin "1") (pinfunction "1_1") (pintype "passive"))
      (node (ref "SD-4") (pin "3") (pinfunction "3_3") (pintype "passive"))
    )
    (net (code "78") (name "Net-(R26-Pad1)") (class "Default")
      (node (ref "R26") (pin "1") (pinfunction "1_1") (pintype "passive"))
      (node (ref "SD-4") (pin "4") (pinfunction "4_4") (pintype "passive"))
    )
    (net (code "79") (name "Net-(R27-Pad1)") (class "Default")
      (node (ref "R27") (pin "1") (pinfunction "1_1") (pintype "passive"))
      (node (ref "SD-5") (pin "1") (pinfunction "1_1") (pintype "passive"))
    )
    (net (code "80") (name "Net-(R28-Pad1)") (class "Default")
      (node (ref "R28") (pin "1") (pinfunction "1_1") (pintype "passive"))
      (node (ref "SD-5") (pin "2") (pinfunction "2_2") (pintype "passive"))
    )
    (net (code "81") (name "Net-(R29-Pad1)") (class "Default")
      (node (ref "R29") (pin "1") (pinfunction "1_1") (pintype "passive"))
      (node (ref "SD-5") (pin "3") (pinfunction "3_3") (pintype "passive"))
    )
    (net (code "82") (name "Net-(R30-Pad1)") (class "Default")
      (node (ref "R30") (pin "1") (pinfunction "1_1") (pintype "passive"))
      (node (ref "SD-5") (pin "4") (pinfunction "4_4") (pintype "passive"))
    )
    (net (code "83") (name "Net-(R31-Pad1)") (class "Default")
      (node (ref "R31") (pin "1") (pinfunction "1_1") (pintype "passive"))
      (node (ref "SD-6") (pin "1") (pinfunction "1_1") (pintype "passive"))
    )
    (net (code "84") (name "Net-(R32-Pad1)") (class "Default")
      (node (ref "R32") (pin "1") (pinfunction "1_1") (pintype "passive"))
      (node (ref "SD-6") (pin "2") (pinfunction "2_2") (pintype "passive"))
    )
    (net (code "85") (name "Net-(R33-Pad1)") (class "Default")
      (node (ref "R33") (pin "1") (pinfunction "1_1") (pintype "passive"))
      (node (ref "SD-6") (pin "3") (pinfunction "3_3") (pintype "passive"))
    )
    (net (code "86") (name "Net-(R34-Pad1)") (class "Default")
      (node (ref "R34") (pin "1") (pinfunction "1_1") (pintype "passive"))
      (node (ref "SD-6") (pin "4") (pinfunction "4_4") (pintype "passive"))
    )
    (net (code "87") (name "Net-(R35-Pad1)") (class "Default")
      (node (ref "R35") (pin "1") (pinfunction "1_1") (pintype "passive"))
      (node (ref "SD-7") (pin "1") (pinfunction "1_1") (pintype "passive"))
    )
    (net (code "88") (name "Net-(R36-Pad1)") (class "Default")
      (node (ref "R36") (pin "1") (pinfunction "1_1") (pintype "passive"))
      (node (ref "SD-7") (pin "2") (pinfunction "2_2") (pintype "passive"))
    )
    (net (code "89") (name "Net-(R37-Pad1)") (class "Default")
      (node (ref "R37") (pin "1") (pinfunction "1_1") (pintype "passive"))
      (node (ref "SD-7") (pin "3") (pinfunction "3_3") (pintype "passive"))
    )
    (net (code "90") (name "Net-(R38-Pad1)") (class "Default")
      (node (ref "R38") (pin "1") (pinfunction "1_1") (pintype "passive"))
      (node (ref "SD-7") (pin "4") (pinfunction "4_4") (pintype "passive"))
    )
    (net (code "91") (name "VCC") (class "Default")
      (node (ref "ATMEGA328") (pin "18") (pinfunction "AVCC_18") (pintype "passive"))
      (node (ref "ATMEGA328") (pin "20") (pinfunction "AREF_20") (pintype "passive"))
      (node (ref "ATMEGA328") (pin "4") (pinfunction "VCC_4") (pintype "power_in"))
      (node (ref "ATMEGA328") (pin "6") (pinfunction "VCC_6") (pintype "power_in"))
      (node (ref "C3") (pin "2") (pinfunction "2_2") (pintype "passive"))
      (node (ref "JP1") (pin "4") (pinfunction "4_4") (pintype "passive"))
      (node (ref "R1") (pin "2") (pinfunction "2_2") (pintype "passive"))
      (node (ref "R4") (pin "2") (pinfunction "2_2") (pintype "passive"))
      (node (ref "SV4") (pin "2") (pinfunction "2_2") (pintype "passive"))
      (node (ref "USB_RASP") (pin "1") (pinfunction "1_1") (pintype "passive"))
    )
    (net (code "92") (name "unconnected-(ATMEGA328-ADC6-Pad19)") (class "Default")
      (node (ref "ATMEGA328") (pin "19") (pinfunction "ADC6_19") (pintype "passive"))
    )
    (net (code "93") (name "unconnected-(ATMEGA328-ADC7-Pad22)") (class "Default")
      (node (ref "ATMEGA328") (pin "22") (pinfunction "ADC7_22") (pintype "passive"))
    )
    (net (code "94") (name "unconnected-(ATMEGA328-PC0(ADC0{slash}PCINT8)-Pad23)") (class "Default")
      (node (ref "ATMEGA328") (pin "23") (pinfunction "PC0(ADC0/PCINT8)_23") (pintype "bidirectional"))
    )
    (net (code "95") (name "unconnected-(ATMEGA328-PC2(ADC2{slash}PCINT10)-Pad25)") (class "Default")
      (node (ref "ATMEGA328") (pin "25") (pinfunction "PC2(ADC2/PCINT10)_25") (pintype "bidirectional"))
    )
    (net (code "96") (name "unconnected-(ATMEGA328-PC3(ADC3{slash}PCINT11)-Pad26)") (class "Default")
      (node (ref "ATMEGA328") (pin "26") (pinfunction "PC3(ADC3/PCINT11)_26") (pintype "bidirectional"))
    )
    (net (code "97") (name "unconnected-(ATMEGA328-PD2(INT0{slash}PCINT18)-Pad32)") (class "Default")
      (node (ref "ATMEGA328") (pin "32") (pinfunction "PD2(INT0/PCINT18)_32") (pintype "bidirectional"))
    )
    (net (code "98") (name "unconnected-(ATMEGA328-PD3(INT1{slash}OC2B{slash}PCINT19)-Pad1)") (class "Default")
      (node (ref "ATMEGA328") (pin "1") (pinfunction "PD3(INT1/OC2B/PCINT19)_1") (pintype "bidirectional"))
    )
    (net (code "99") (name "unconnected-(ATMEGA328-PD4(T0{slash}XCK{slash}PCINT20)-Pad2)") (class "Default")
      (node (ref "ATMEGA328") (pin "2") (pinfunction "PD4(T0/XCK/PCINT20)_2") (pintype "bidirectional"))
    )
    (net (code "100") (name "unconnected-(ATMEGA328-PD5(T1{slash}OC0B{slash}PCINT21)-Pad9)") (class "Default")
      (node (ref "ATMEGA328") (pin "9") (pinfunction "PD5(T1/OC0B/PCINT21)_9") (pintype "bidirectional"))
    )
    (net (code "101") (name "unconnected-(ATMEGA328-PD6(AIN0{slash}OC0A{slash}PCINT22)-Pad10)") (class "Default")
      (node (ref "ATMEGA328") (pin "10") (pinfunction "PD6(AIN0/OC0A/PCINT22)_10") (pintype "bidirectional"))
    )
  )
)
